# v1.net
KiCad netlist of a schematic drawn in EAGLE
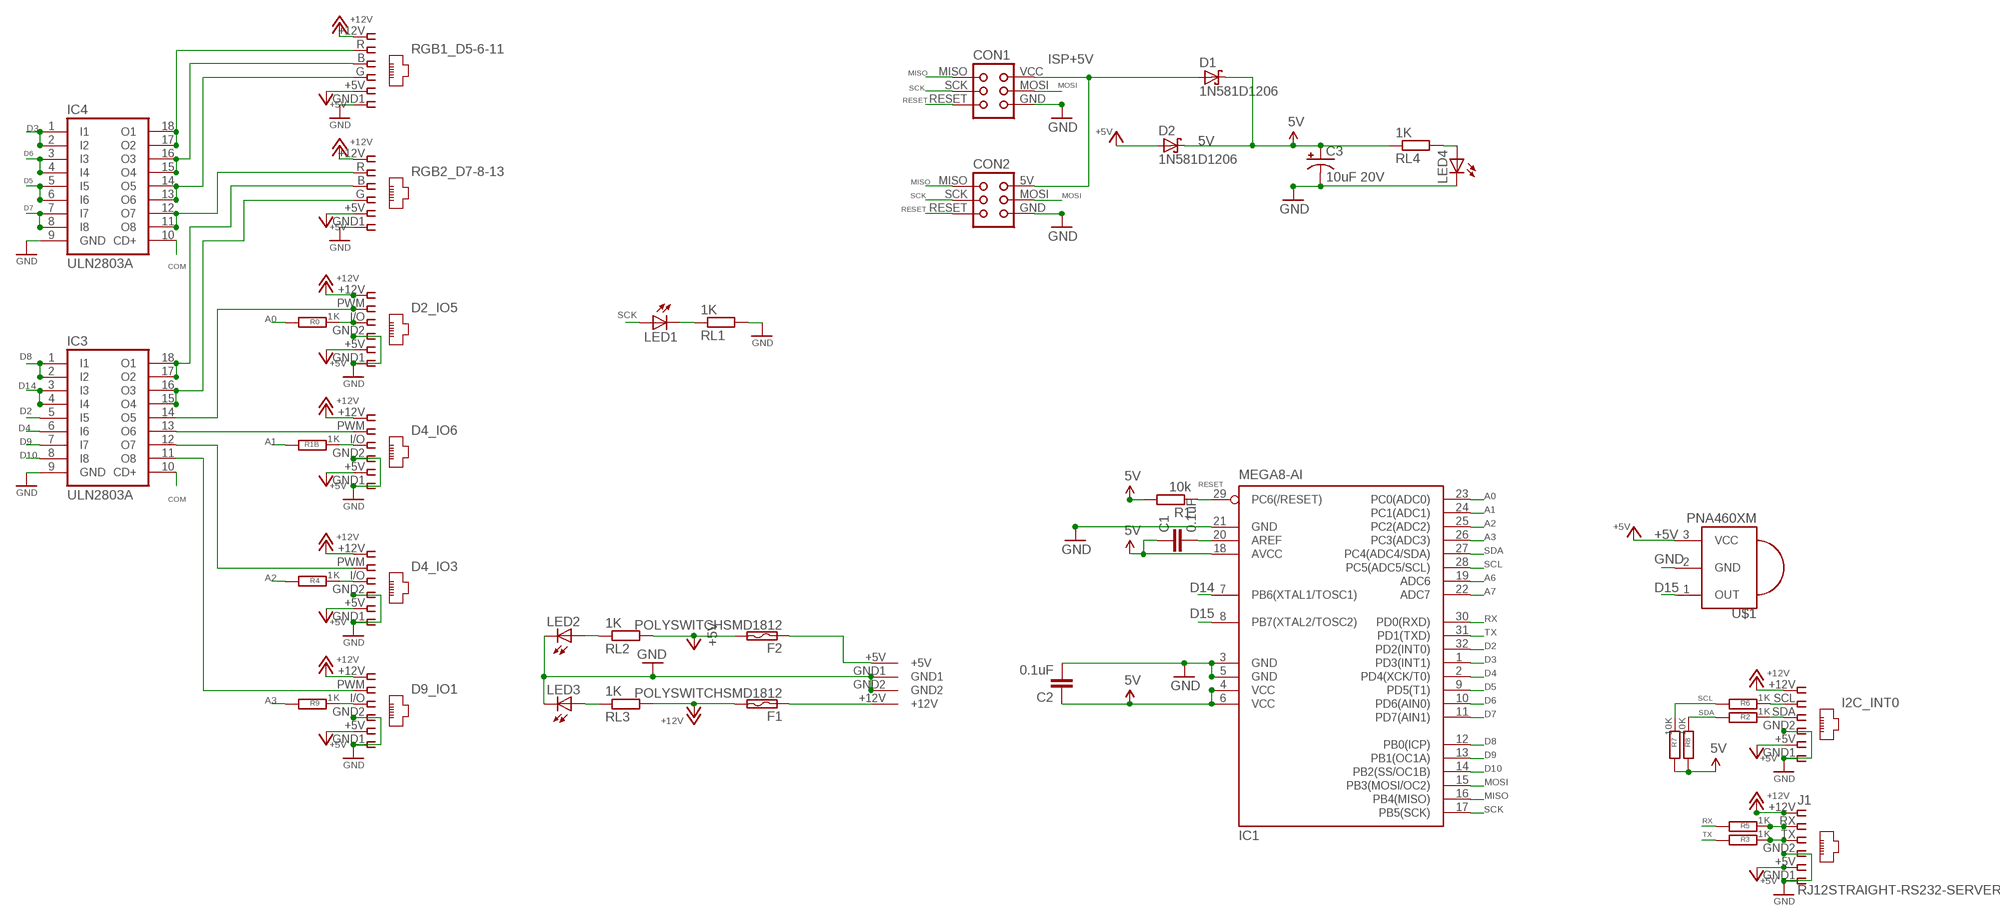
[diagram p0: schematic, sheet 1]

(export (version "E")
  (design (tool "Eeschema 10.0.6"))
  (components
    (comp (ref "C1")
      (value "0.1uF")
      (footprint "eagle-import:C1206")
      (libsource (lib "eagle-import") (part "C-EUC1206"))
    )
    (comp (ref "C2")
      (value "0.1uF")
      (footprint "eagle-import:C1206")
      (libsource (lib "eagle-import") (part "C-EUC1206"))
    )
    (comp (ref "C3")
      (value "10uF 20V")
      (footprint "eagle-import:EIA3216-KIT")
      (libsource (lib "eagle-import") (part "CAP_POL1206-KIT"))
    )
    (comp (ref "CON1")
      (value "TINYISP")
      (footprint "eagle-import:TINYISP")
      (libsource (lib "eagle-import") (part "TINYISP"))
    )
    (comp (ref "CON2")
      (value "TINYISPTAG")
      (footprint "eagle-import:TC2030-MCP")
      (libsource (lib "eagle-import") (part "TINYISPTAG"))
    )
    (comp (ref "D1")
      (value "1N581D1206")
      (footprint "eagle-import:LED-1206")
      (libsource (lib "eagle-import") (part "1N581D1206"))
    )
    (comp (ref "D2")
      (value "1N581D1206")
      (footprint "eagle-import:LED-1206")
      (libsource (lib "eagle-import") (part "1N581D1206"))
    )
    (comp (ref "D2_IO5")
      (value "IO5")
      (footprint "eagle-import:RJ12-STRAIGHT")
      (libsource (lib "eagle-import") (part "RJ12STRAIGHT"))
    )
    (comp (ref "D4_IO3")
      (value "IO3")
      (footprint "eagle-import:RJ12-STRAIGHT")
      (libsource (lib "eagle-import") (part "RJ12STRAIGHT"))
    )
    (comp (ref "D4_IO6")
      (value "IO6")
      (footprint "eagle-import:RJ12-STRAIGHT")
      (libsource (lib "eagle-import") (part "RJ12STRAIGHT"))
    )
    (comp (ref "D9_IO1")
      (value "IO1")
      (footprint "eagle-import:RJ12-STRAIGHT")
      (libsource (lib "eagle-import") (part "RJ12STRAIGHT"))
    )
    (comp (ref "F1")
      (value "POLYSWITCHSMD1812")
      (footprint "eagle-import:C1812")
      (libsource (lib "eagle-import") (part "POLYSWITCHSMD1812"))
    )
    (comp (ref "F2")
      (value "POLYSWITCHSMD1812")
      (footprint "eagle-import:C1812")
      (libsource (lib "eagle-import") (part "POLYSWITCHSMD1812"))
    )
    (comp (ref "I2C_INT0")
      (value "I2C")
      (footprint "eagle-import:RJ12-STRAIGHT-I2C")
      (libsource (lib "eagle-import") (part "RJ12STRAIGHT-I2C"))
    )
    (comp (ref "IC1")
      (value "MEGA8-AI")
      (footprint "eagle-import:TQFP32-08")
      (fields (field (name "MPN") "ATMEGA8-16AU"))
      (libsource (lib "eagle-import") (part "MEGA8-AI"))
    )
    (comp (ref "IC3")
      (value "ULN2803A")
      (footprint "eagle-import:SO18W")
      (libsource (lib "eagle-import") (part "ULN2803A"))
    )
    (comp (ref "IC4")
      (value "ULN2803A")
      (footprint "eagle-import:SO18W")
      (libsource (lib "eagle-import") (part "ULN2803A"))
    )
    (comp (ref "J1")
      (value "RJ12STRAIGHT-RS232-SERVER")
      (footprint "eagle-import:RJ12-STRAIGHT-RS232")
      (libsource (lib "eagle-import") (part "RJ12STRAIGHT-RS232-SERVER"))
    )
    (comp (ref "LED1")
      (value "LED3MM")
      (footprint "eagle-import:LED3MM")
      (libsource (lib "eagle-import") (part "LED3MM"))
    )
    (comp (ref "LED2")
      (value "LED3MM")
      (footprint "eagle-import:LED3MM")
      (libsource (lib "eagle-import") (part "LED3MM"))
    )
    (comp (ref "LED3")
      (value "LED3MM")
      (footprint "eagle-import:LED3MM")
      (libsource (lib "eagle-import") (part "LED3MM"))
    )
    (comp (ref "LED4")
      (value "LED3MM")
      (footprint "eagle-import:LED3MM")
      (libsource (lib "eagle-import") (part "LED3MM"))
    )
    (comp (ref "R0")
      (value "1K")
      (footprint "eagle-import:M1206")
      (libsource (lib "eagle-import") (part "R-EU_M1206"))
    )
    (comp (ref "R1")
      (value "10k")
      (footprint "eagle-import:M1206")
      (libsource (lib "eagle-import") (part "R-EU_M1206"))
    )
    (comp (ref "R1B")
      (value "1K")
      (footprint "eagle-import:M1206")
      (libsource (lib "eagle-import") (part "R-EU_M1206"))
    )
    (comp (ref "R2")
      (value "1K")
      (footprint "eagle-import:M1206")
      (libsource (lib "eagle-import") (part "R-EU_M1206"))
    )
    (comp (ref "R3")
      (value "1K")
      (footprint "eagle-import:M1206")
      (libsource (lib "eagle-import") (part "R-EU_M1206"))
    )
    (comp (ref "R4")
      (value "1K")
      (footprint "eagle-import:M1206")
      (libsource (lib "eagle-import") (part "R-EU_M1206"))
    )
    (comp (ref "R5")
      (value "1K")
      (footprint "eagle-import:M1206")
      (libsource (lib "eagle-import") (part "R-EU_M1206"))
    )
    (comp (ref "R6")
      (value "1K")
      (footprint "eagle-import:M1206")
      (libsource (lib "eagle-import") (part "R-EU_M1206"))
    )
    (comp (ref "R7")
      (value "10K")
      (footprint "eagle-import:M1206")
      (libsource (lib "eagle-import") (part "R-EU_M1206"))
    )
    (comp (ref "R8")
      (value "10K")
      (footprint "eagle-import:M1206")
      (libsource (lib "eagle-import") (part "R-EU_M1206"))
    )
    (comp (ref "R9")
      (value "1K")
      (footprint "eagle-import:M1206")
      (libsource (lib "eagle-import") (part "R-EU_M1206"))
    )
    (comp (ref "RGB1_D5-6-11")
      (value "RGB1")
      (footprint "eagle-import:RJ12-STRAIGHT-RGB")
      (libsource (lib "eagle-import") (part "RJ12STRAIGHT-RGB"))
    )
    (comp (ref "RGB2_D7-8-13")
      (value "RGB2")
      (footprint "eagle-import:RJ12-STRAIGHT-RGB")
      (libsource (lib "eagle-import") (part "RJ12STRAIGHT-RGB"))
    )
    (comp (ref "RL1")
      (value "1K")
      (footprint "eagle-import:M1206")
      (libsource (lib "eagle-import") (part "R-EU_M1206"))
    )
    (comp (ref "RL2")
      (value "1K")
      (footprint "eagle-import:M1206")
      (libsource (lib "eagle-import") (part "R-EU_M1206"))
    )
    (comp (ref "RL3")
      (value "1K")
      (footprint "eagle-import:M1206")
      (libsource (lib "eagle-import") (part "R-EU_M1206"))
    )
    (comp (ref "RL4")
      (value "1K")
      (footprint "eagle-import:M1206")
      (libsource (lib "eagle-import") (part "R-EU_M1206"))
    )
    (comp (ref "U$1")
      (value "PNA460XM")
      (footprint "eagle-import:PNA460XM")
      (libsource (lib "eagle-import") (part "PNA460XM"))
    )
    (comp (ref "U$2")
      (value "KPJX-4S-S")
      (footprint "eagle-import:KPJX-4S-S")
      (libsource (lib "eagle-import") (part "KPJX-4S-S"))
    )
  )
  (nets
    (net (code "1") (name "+5V") (class "Default")
      (node (ref "D2") (pin "A") (pinfunction "A_A") (pintype "passive"))
      (node (ref "D2_IO5") (pin "+5V") (pinfunction "5_+5V") (pintype "power_in"))
      (node (ref "D4_IO3") (pin "+5V") (pinfunction "5_+5V") (pintype "power_in"))
      (node (ref "D4_IO6") (pin "+5V") (pinfunction "5_+5V") (pintype "power_in"))
      (node (ref "D9_IO1") (pin "+5V") (pinfunction "5_+5V") (pintype "power_in"))
      (node (ref "F2") (pin "2") (pinfunction "2_2") (pintype "passive"))
      (node (ref "I2C_INT0") (pin "+5V") (pinfunction "5_+5V") (pintype "power_in"))
      (node (ref "J1") (pin "+5V") (pinfunction "5_+5V") (pintype "power_in"))
      (node (ref "RGB1_D5-6-11") (pin "+5V") (pinfunction "5_+5V") (pintype "power_in"))
      (node (ref "RGB2_D7-8-13") (pin "+5V") (pinfunction "5_+5V") (pintype "power_in"))
      (node (ref "RL2") (pin "2") (pinfunction "2_2") (pintype "passive"))
      (node (ref "U$1") (pin "3") (pinfunction "VCC_3") (pintype "power_in"))
    )
    (net (code "2") (name "+12V") (class "Default")
      (node (ref "D2_IO5") (pin "+12V") (pinfunction "1_+12V") (pintype "power_in"))
      (node (ref "D4_IO3") (pin "+12V") (pinfunction "1_+12V") (pintype "power_in"))
      (node (ref "D4_IO6") (pin "+12V") (pinfunction "1_+12V") (pintype "power_in"))
      (node (ref "D9_IO1") (pin "+12V") (pinfunction "1_+12V") (pintype "power_in"))
      (node (ref "F1") (pin "2") (pinfunction "2_2") (pintype "passive"))
      (node (ref "I2C_INT0") (pin "+12V") (pinfunction "1_+12V") (pintype "power_in"))
      (node (ref "J1") (pin "+12V") (pinfunction "1_+12V") (pintype "power_in"))
      (node (ref "RGB1_D5-6-11") (pin "+12V") (pinfunction "1_+12V") (pintype "power_in"))
      (node (ref "RGB2_D7-8-13") (pin "+12V") (pinfunction "1_+12V") (pintype "power_in"))
      (node (ref "RL3") (pin "2") (pinfunction "2_2") (pintype "passive"))
    )
    (net (code "3") (name "/A0") (class "Default")
      (node (ref "IC1") (pin "23") (pinfunction "PC0(ADC0)_23") (pintype "bidirectional"))
      (node (ref "R0") (pin "2") (pinfunction "2_2") (pintype "passive"))
    )
    (net (code "4") (name "/A1") (class "Default")
      (node (ref "IC1") (pin "24") (pinfunction "PC1(ADC1)_24") (pintype "bidirectional"))
      (node (ref "R1B") (pin "2") (pinfunction "2_2") (pintype "passive"))
    )
    (net (code "5") (name "/A2") (class "Default")
      (node (ref "IC1") (pin "25") (pinfunction "PC2(ADC2)_25") (pintype "bidirectional"))
      (node (ref "R4") (pin "2") (pinfunction "2_2") (pintype "passive"))
    )
    (net (code "6") (name "/A3") (class "Default")
      (node (ref "IC1") (pin "26") (pinfunction "PC3(ADC3)_26") (pintype "bidirectional"))
      (node (ref "R9") (pin "2") (pinfunction "2_2") (pintype "passive"))
    )
    (net (code "7") (name "/A6") (class "Default")
      (node (ref "IC1") (pin "19") (pinfunction "ADC6_19") (pintype "bidirectional"))
    )
    (net (code "8") (name "/A7") (class "Default")
      (node (ref "IC1") (pin "22") (pinfunction "ADC7_22") (pintype "bidirectional"))
    )
    (net (code "9") (name "/COM") (class "Default")
      (node (ref "IC3") (pin "10") (pinfunction "CD+_10") (pintype "passive"))
      (node (ref "IC4") (pin "10") (pinfunction "CD+_10") (pintype "passive"))
    )
    (net (code "10") (name "/D2") (class "Default")
      (node (ref "IC1") (pin "32") (pinfunction "PD2(INT0)_32") (pintype "bidirectional"))
      (node (ref "IC3") (pin "5") (pinfunction "I5_5") (pintype "input"))
    )
    (net (code "11") (name "/D3") (class "Default")
      (node (ref "IC1") (pin "1") (pinfunction "PD3(INT1)_1") (pintype "bidirectional"))
      (node (ref "IC4") (pin "1") (pinfunction "I1_1") (pintype "input"))
      (node (ref "IC4") (pin "2") (pinfunction "I2_2") (pintype "input"))
    )
    (net (code "12") (name "/D4") (class "Default")
      (node (ref "IC1") (pin "2") (pinfunction "PD4(XCK/T0)_2") (pintype "bidirectional"))
      (node (ref "IC3") (pin "6") (pinfunction "I6_6") (pintype "input"))
    )
    (net (code "13") (name "/D5") (class "Default")
      (node (ref "IC1") (pin "9") (pinfunction "PD5(T1)_9") (pintype "bidirectional"))
      (node (ref "IC4") (pin "5") (pinfunction "I5_5") (pintype "input"))
      (node (ref "IC4") (pin "6") (pinfunction "I6_6") (pintype "input"))
    )
    (net (code "14") (name "/D6") (class "Default")
      (node (ref "IC1") (pin "10") (pinfunction "PD6(AIN0)_10") (pintype "bidirectional"))
      (node (ref "IC4") (pin "3") (pinfunction "I3_3") (pintype "input"))
      (node (ref "IC4") (pin "4") (pinfunction "I4_4") (pintype "input"))
    )
    (net (code "15") (name "/D7") (class "Default")
      (node (ref "IC1") (pin "11") (pinfunction "PD7(AIN1)_11") (pintype "bidirectional"))
      (node (ref "IC4") (pin "7") (pinfunction "I7_7") (pintype "input"))
      (node (ref "IC4") (pin "8") (pinfunction "I8_8") (pintype "input"))
    )
    (net (code "16") (name "/D8") (class "Default")
      (node (ref "IC1") (pin "12") (pinfunction "PB0(ICP)_12") (pintype "bidirectional"))
      (node (ref "IC3") (pin "1") (pinfunction "I1_1") (pintype "input"))
      (node (ref "IC3") (pin "2") (pinfunction "I2_2") (pintype "input"))
    )
    (net (code "17") (name "/D9") (class "Default")
      (node (ref "IC1") (pin "13") (pinfunction "PB1(OC1A)_13") (pintype "bidirectional"))
      (node (ref "IC3") (pin "7") (pinfunction "I7_7") (pintype "input"))
    )
    (net (code "18") (name "/D10") (class "Default")
      (node (ref "IC1") (pin "14") (pinfunction "PB2(SS/OC1B)_14") (pintype "bidirectional"))
      (node (ref "IC3") (pin "8") (pinfunction "I8_8") (pintype "input"))
    )
    (net (code "19") (name "/D14") (class "Default")
      (node (ref "IC1") (pin "7") (pinfunction "PB6(XTAL1/TOSC1)_7") (pintype "bidirectional"))
      (node (ref "IC3") (pin "3") (pinfunction "I3_3") (pintype "input"))
      (node (ref "IC3") (pin "4") (pinfunction "I4_4") (pintype "input"))
    )
    (net (code "20") (name "/D15") (class "Default")
      (node (ref "IC1") (pin "8") (pinfunction "PB7(XTAL2/TOSC2)_8") (pintype "bidirectional"))
      (node (ref "U$1") (pin "1") (pinfunction "OUT_1") (pintype "output"))
    )
    (net (code "21") (name "/ISP+5V") (class "Default")
      (node (ref "CON1") (pin "VCC") (pinfunction "VCC_VCC") (pintype "passive"))
      (node (ref "CON2") (pin "5V") (pinfunction "VCC_5V") (pintype "passive"))
      (node (ref "D1") (pin "A") (pinfunction "A_A") (pintype "passive"))
    )
    (net (code "22") (name "/MISO") (class "Default")
      (node (ref "CON1") (pin "MISO") (pinfunction "MISO_MISO") (pintype "passive"))
      (node (ref "CON2") (pin "MISO") (pinfunction "MISO_MISO") (pintype "passive"))
      (node (ref "IC1") (pin "16") (pinfunction "PB4(MISO)_16") (pintype "bidirectional"))
    )
    (net (code "23") (name "/MOSI") (class "Default")
      (node (ref "CON1") (pin "MOSI") (pinfunction "MOSI_MOSI") (pintype "passive"))
      (node (ref "CON2") (pin "MOSI") (pinfunction "MOSI_MOSI") (pintype "passive"))
      (node (ref "IC1") (pin "15") (pinfunction "PB3(MOSI/OC2)_15") (pintype "bidirectional"))
    )
    (net (code "24") (name "/RESET") (class "Default")
      (node (ref "CON1") (pin "RESET") (pinfunction "RESET_RESET") (pintype "passive"))
      (node (ref "CON2") (pin "RESET") (pinfunction "RESET_RESET") (pintype "passive"))
      (node (ref "IC1") (pin "29") (pinfunction "PC6(/RESET)_29") (pintype "bidirectional"))
      (node (ref "R1") (pin "1") (pinfunction "1_1") (pintype "passive"))
    )
    (net (code "25") (name "/RX") (class "Default")
      (node (ref "IC1") (pin "30") (pinfunction "PD0(RXD)_30") (pintype "bidirectional"))
      (node (ref "R5") (pin "2") (pinfunction "2_2") (pintype "passive"))
    )
    (net (code "26") (name "/SCK") (class "Default")
      (node (ref "CON1") (pin "SCK") (pinfunction "SCK_SCK") (pintype "passive"))
      (node (ref "CON2") (pin "SCK") (pinfunction "SCK_SCK") (pintype "passive"))
      (node (ref "IC1") (pin "17") (pinfunction "PB5(SCK)_17") (pintype "bidirectional"))
      (node (ref "LED1") (pin "A") (pinfunction "A_A") (pintype "passive"))
    )
    (net (code "27") (name "/SCL") (class "Default")
      (node (ref "IC1") (pin "28") (pinfunction "PC5(ADC5/SCL)_28") (pintype "bidirectional"))
      (node (ref "R6") (pin "2") (pinfunction "2_2") (pintype "passive"))
      (node (ref "R7") (pin "1") (pinfunction "1_1") (pintype "passive"))
    )
    (net (code "28") (name "/SDA") (class "Default")
      (node (ref "IC1") (pin "27") (pinfunction "PC4(ADC4/SDA)_27") (pintype "bidirectional"))
      (node (ref "R2") (pin "2") (pinfunction "2_2") (pintype "passive"))
      (node (ref "R8") (pin "1") (pinfunction "1_1") (pintype "passive"))
    )
    (net (code "29") (name "/TX") (class "Default")
      (node (ref "IC1") (pin "31") (pinfunction "PD1(TXD)_31") (pintype "bidirectional"))
      (node (ref "R3") (pin "2") (pinfunction "2_2") (pintype "passive"))
    )
    (net (code "30") (name "5V") (class "Default")
      (node (ref "C1") (pin "1") (pinfunction "1_1") (pintype "passive"))
      (node (ref "C2") (pin "1") (pinfunction "1_1") (pintype "passive"))
      (node (ref "C3") (pin "A") (pinfunction "+_A") (pintype "passive"))
      (node (ref "D1") (pin "C") (pinfunction "C_C") (pintype "passive"))
      (node (ref "D2") (pin "C") (pinfunction "C_C") (pintype "passive"))
      (node (ref "IC1") (pin "18") (pinfunction "AVCC_18") (pintype "power_in"))
      (node (ref "IC1") (pin "4") (pinfunction "VCC_4") (pintype "power_in"))
      (node (ref "IC1") (pin "6") (pinfunction "VCC_6") (pintype "power_in"))
      (node (ref "R1") (pin "2") (pinfunction "2_2") (pintype "passive"))
      (node (ref "R7") (pin "2") (pinfunction "2_2") (pintype "passive"))
      (node (ref "R8") (pin "2") (pinfunction "2_2") (pintype "passive"))
      (node (ref "RL4") (pin "1") (pinfunction "1_1") (pintype "passive"))
    )
    (net (code "31") (name "GND") (class "Default")
      (node (ref "C2") (pin "2") (pinfunction "2_2") (pintype "passive"))
      (node (ref "C3") (pin "C") (pinfunction "-_C") (pintype "passive"))
      (node (ref "CON1") (pin "GND") (pinfunction "GND_GND") (pintype "passive"))
      (node (ref "CON2") (pin "GND") (pinfunction "GND_GND") (pintype "passive"))
      (node (ref "D2_IO5") (pin "GND1") (pinfunction "6_GND1") (pintype "power_in"))
      (node (ref "D2_IO5") (pin "GND2") (pinfunction "4_GND2") (pintype "power_in"))
      (node (ref "D4_IO3") (pin "GND1") (pinfunction "6_GND1") (pintype "power_in"))
      (node (ref "D4_IO3") (pin "GND2") (pinfunction "4_GND2") (pintype "power_in"))
      (node (ref "D4_IO6") (pin "GND1") (pinfunction "6_GND1") (pintype "power_in"))
      (node (ref "D4_IO6") (pin "GND2") (pinfunction "4_GND2") (pintype "power_in"))
      (node (ref "D9_IO1") (pin "GND1") (pinfunction "6_GND1") (pintype "power_in"))
      (node (ref "D9_IO1") (pin "GND2") (pinfunction "4_GND2") (pintype "power_in"))
      (node (ref "I2C_INT0") (pin "GND1") (pinfunction "6_GND1") (pintype "power_in"))
      (node (ref "I2C_INT0") (pin "GND2") (pinfunction "4_GND2") (pintype "power_in"))
      (node (ref "IC1") (pin "21") (pinfunction "GND_21") (pintype "power_in"))
      (node (ref "IC1") (pin "3") (pinfunction "GND_3") (pintype "power_in"))
      (node (ref "IC1") (pin "5") (pinfunction "GND_5") (pintype "power_in"))
      (node (ref "IC3") (pin "9") (pinfunction "GND_9") (pintype "power_in"))
      (node (ref "IC4") (pin "9") (pinfunction "GND_9") (pintype "power_in"))
      (node (ref "J1") (pin "GND1") (pinfunction "6_GND1") (pintype "power_in"))
      (node (ref "J1") (pin "GND2") (pinfunction "4_GND2") (pintype "power_in"))
      (node (ref "LED2") (pin "K") (pinfunction "C_K") (pintype "passive"))
      (node (ref "LED3") (pin "K") (pinfunction "C_K") (pintype "passive"))
      (node (ref "LED4") (pin "K") (pinfunction "C_K") (pintype "passive"))
      (node (ref "RGB1_D5-6-11") (pin "GND1") (pinfunction "6_GND1") (pintype "power_in"))
      (node (ref "RGB2_D7-8-13") (pin "GND1") (pinfunction "6_GND1") (pintype "power_in"))
      (node (ref "RL1") (pin "2") (pinfunction "2_2") (pintype "passive"))
      (node (ref "U$1") (pin "2") (pinfunction "GND_2") (pintype "power_in"))
      (node (ref "U$2") (pin "GND1") (pinfunction "GND1_GND1") (pintype "input"))
      (node (ref "U$2") (pin "GND2") (pinfunction "GND2_GND2") (pintype "input"))
    )
    (net (code "32") (name "Net-(D2_IO5-2)") (class "Default")
      (node (ref "D2_IO5") (pin "PWM") (pinfunction "2_PWM") (pintype "bidirectional"))
      (node (ref "IC3") (pin "14") (pinfunction "O5_14") (pintype "open_collector"))
    )
    (net (code "33") (name "Net-(D2_IO5-3)") (class "Default")
      (node (ref "D2_IO5") (pin "I/O") (pinfunction "3_I/O") (pintype "bidirectional"))
      (node (ref "R0") (pin "1") (pinfunction "1_1") (pintype "passive"))
    )
    (net (code "34") (name "Net-(D4_IO3-2)") (class "Default")
      (node (ref "D4_IO3") (pin "PWM") (pinfunction "2_PWM") (pintype "bidirectional"))
      (node (ref "IC3") (pin "12") (pinfunction "O7_12") (pintype "open_collector"))
    )
    (net (code "35") (name "Net-(D4_IO3-3)") (class "Default")
      (node (ref "D4_IO3") (pin "I/O") (pinfunction "3_I/O") (pintype "bidirectional"))
      (node (ref "R4") (pin "1") (pinfunction "1_1") (pintype "passive"))
    )
    (net (code "36") (name "Net-(D4_IO6-2)") (class "Default")
      (node (ref "D4_IO6") (pin "PWM") (pinfunction "2_PWM") (pintype "bidirectional"))
      (node (ref "IC3") (pin "13") (pinfunction "O6_13") (pintype "open_collector"))
    )
    (net (code "37") (name "Net-(D4_IO6-3)") (class "Default")
      (node (ref "D4_IO6") (pin "I/O") (pinfunction "3_I/O") (pintype "bidirectional"))
      (node (ref "R1B") (pin "1") (pinfunction "1_1") (pintype "passive"))
    )
    (net (code "38") (name "Net-(D9_IO1-2)") (class "Default")
      (node (ref "D9_IO1") (pin "PWM") (pinfunction "2_PWM") (pintype "bidirectional"))
      (node (ref "IC3") (pin "11") (pinfunction "O8_11") (pintype "open_collector"))
    )
    (net (code "39") (name "Net-(D9_IO1-3)") (class "Default")
      (node (ref "D9_IO1") (pin "I/O") (pinfunction "3_I/O") (pintype "bidirectional"))
      (node (ref "R9") (pin "1") (pinfunction "1_1") (pintype "passive"))
    )
    (net (code "40") (name "Net-(F1-Pad1)") (class "Default")
      (node (ref "F1") (pin "1") (pinfunction "1_1") (pintype "passive"))
      (node (ref "U$2") (pin "+12V") (pinfunction "+12V_+12V") (pintype "power_in"))
    )
    (net (code "41") (name "Net-(F2-Pad1)") (class "Default")
      (node (ref "F2") (pin "1") (pinfunction "1_1") (pintype "passive"))
      (node (ref "U$2") (pin "+5V") (pinfunction "+5V_+5V") (pintype "power_in"))
    )
    (net (code "42") (name "Net-(I2C_INT0-2)") (class "Default")
      (node (ref "I2C_INT0") (pin "SCL") (pinfunction "2_SCL") (pintype "bidirectional"))
      (node (ref "R6") (pin "1") (pinfunction "1_1") (pintype "passive"))
    )
    (net (code "43") (name "Net-(I2C_INT0-3)") (class "Default")
      (node (ref "I2C_INT0") (pin "SDA") (pinfunction "3_SDA") (pintype "bidirectional"))
      (node (ref "R2") (pin "1") (pinfunction "1_1") (pintype "passive"))
    )
    (net (code "44") (name "Net-(IC1-AREF)") (class "Default")
      (node (ref "C1") (pin "2") (pinfunction "2_2") (pintype "passive"))
      (node (ref "IC1") (pin "20") (pinfunction "AREF_20") (pintype "passive"))
    )
    (net (code "45") (name "Net-(IC3-O1)") (class "Default")
      (node (ref "IC3") (pin "17") (pinfunction "O2_17") (pintype "open_collector"))
      (node (ref "IC3") (pin "18") (pinfunction "O1_18") (pintype "open_collector"))
      (node (ref "RGB2_D7-8-13") (pin "B") (pinfunction "3_B") (pintype "bidirectional"))
    )
    (net (code "46") (name "Net-(IC3-O3)") (class "Default")
      (node (ref "IC3") (pin "15") (pinfunction "O4_15") (pintype "open_collector"))
      (node (ref "IC3") (pin "16") (pinfunction "O3_16") (pintype "open_collector"))
      (node (ref "RGB2_D7-8-13") (pin "G") (pinfunction "4_G") (pintype "power_in"))
    )
    (net (code "47") (name "Net-(IC4-O1)") (class "Default")
      (node (ref "IC4") (pin "17") (pinfunction "O2_17") (pintype "open_collector"))
      (node (ref "IC4") (pin "18") (pinfunction "O1_18") (pintype "open_collector"))
      (node (ref "RGB1_D5-6-11") (pin "R") (pinfunction "2_R") (pintype "bidirectional"))
    )
    (net (code "48") (name "Net-(IC4-O3)") (class "Default")
      (node (ref "IC4") (pin "15") (pinfunction "O4_15") (pintype "open_collector"))
      (node (ref "IC4") (pin "16") (pinfunction "O3_16") (pintype "open_collector"))
      (node (ref "RGB1_D5-6-11") (pin "B") (pinfunction "3_B") (pintype "bidirectional"))
    )
    (net (code "49") (name "Net-(IC4-O5)") (class "Default")
      (node (ref "IC4") (pin "13") (pinfunction "O6_13") (pintype "open_collector"))
      (node (ref "IC4") (pin "14") (pinfunction "O5_14") (pintype "open_collector"))
      (node (ref "RGB1_D5-6-11") (pin "G") (pinfunction "4_G") (pintype "power_in"))
    )
    (net (code "50") (name "Net-(IC4-O7)") (class "Default")
      (node (ref "IC4") (pin "11") (pinfunction "O8_11") (pintype "open_collector"))
      (node (ref "IC4") (pin "12") (pinfunction "O7_12") (pintype "open_collector"))
      (node (ref "RGB2_D7-8-13") (pin "R") (pinfunction "2_R") (pintype "bidirectional"))
    )
    (net (code "51") (name "Net-(J1-2)") (class "Default")
      (node (ref "J1") (pin "RX") (pinfunction "2_RX") (pintype "bidirectional"))
      (node (ref "R5") (pin "1") (pinfunction "1_1") (pintype "passive"))
    )
    (net (code "52") (name "Net-(J1-3)") (class "Default")
      (node (ref "J1") (pin "TX") (pinfunction "3_TX") (pintype "bidirectional"))
      (node (ref "R3") (pin "1") (pinfunction "1_1") (pintype "passive"))
    )
    (net (code "53") (name "Net-(LED1-C)") (class "Default")
      (node (ref "LED1") (pin "K") (pinfunction "C_K") (pintype "passive"))
      (node (ref "RL1") (pin "1") (pinfunction "1_1") (pintype "passive"))
    )
    (net (code "54") (name "Net-(LED2-PadA)") (class "Default")
      (node (ref "LED2") (pin "A") (pinfunction "A_A") (pintype "passive"))
      (node (ref "RL2") (pin "1") (pinfunction "1_1") (pintype "passive"))
    )
    (net (code "55") (name "Net-(LED3-PadA)") (class "Default")
      (node (ref "LED3") (pin "A") (pinfunction "A_A") (pintype "passive"))
      (node (ref "RL3") (pin "1") (pinfunction "1_1") (pintype "passive"))
    )
    (net (code "56") (name "Net-(LED4-PadA)") (class "Default")
      (node (ref "LED4") (pin "A") (pinfunction "A_A") (pintype "passive"))
      (node (ref "RL4") (pin "2") (pinfunction "2_2") (pintype "passive"))
    )
  )
)
